# SDRAM.net
KiCad netlist of a schematic drawn in Altium Designer
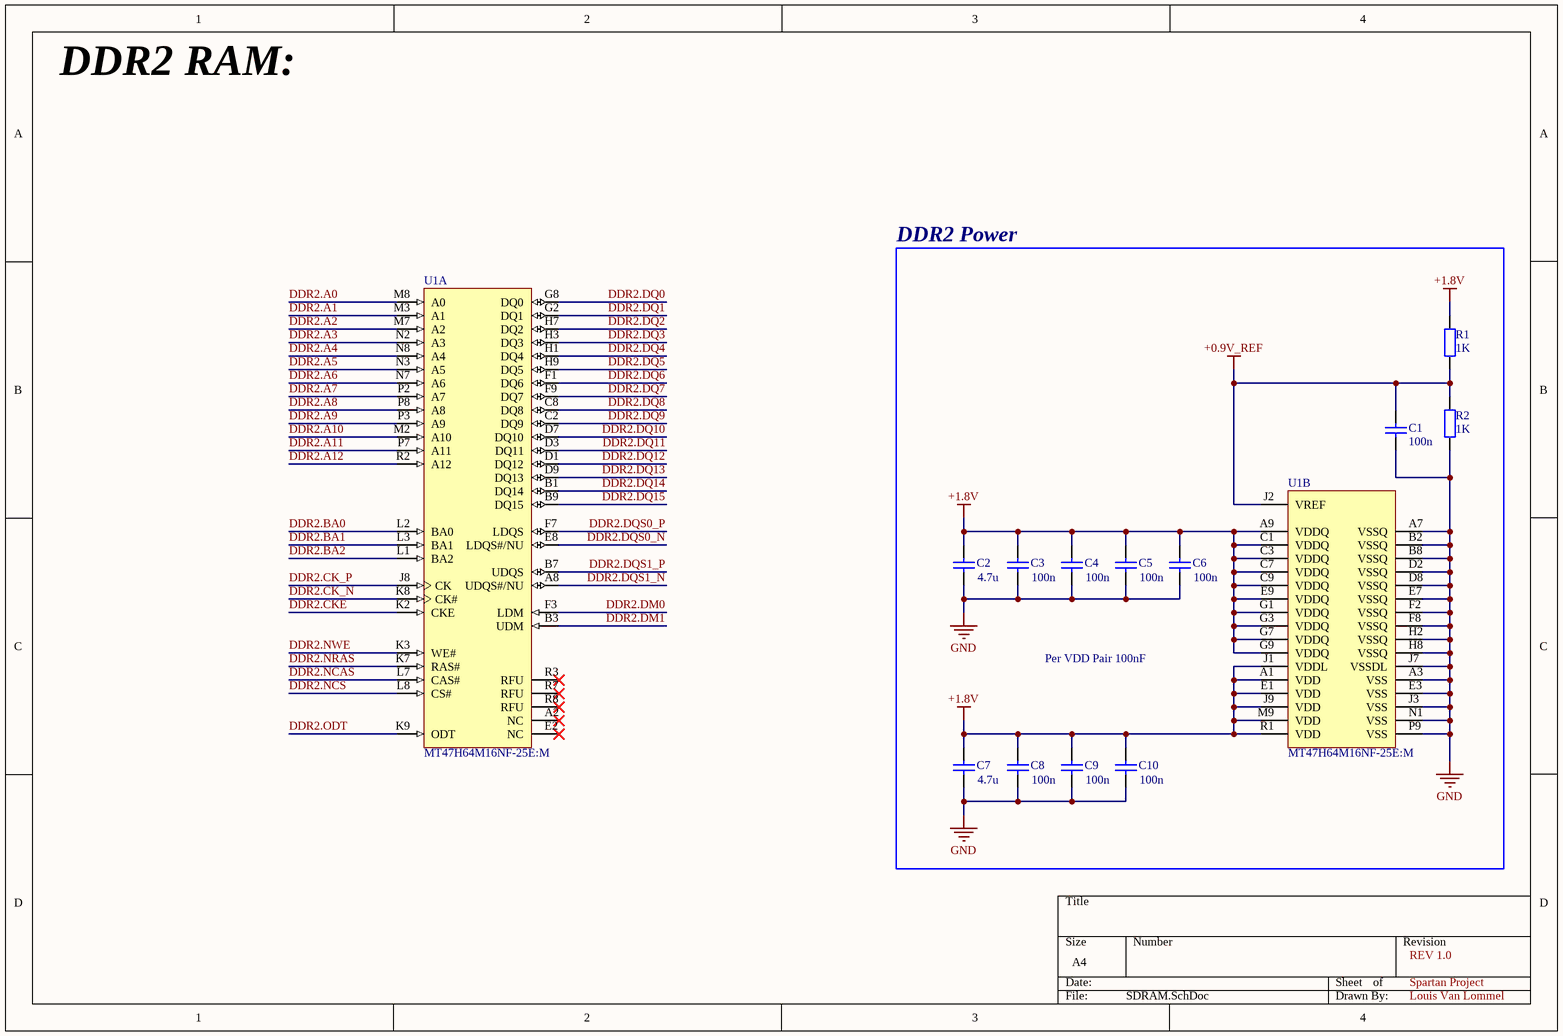
[diagram p0: SDRAM.SchDoc]

(export (version "E")
  (design (tool "Eeschema 10.0.6"))
  (components
    (comp (ref "C1")
      (value "100n")
      (footprint "CAP_0603")
      (description "Capacitor")
      (fields (field (name "PUBLISHER") "Altium Limited"))
      (libsource (lib "Miscellaneous Devices") (part "Cap"))
    )
    (comp (ref "C2")
      (value "4.7u")
      (description "Capacitor")
      (fields (field (name "PUBLISHER") "Altium Limited"))
      (libsource (lib "Miscellaneous Devices") (part "Cap"))
    )
    (comp (ref "C3")
      (value "100n")
      (footprint "CAP_0603")
      (description "Capacitor")
      (fields (field (name "PUBLISHER") "Altium Limited"))
      (libsource (lib "Miscellaneous Devices") (part "Cap"))
    )
    (comp (ref "C4")
      (value "100n")
      (footprint "CAP_0603")
      (description "Capacitor")
      (fields (field (name "PUBLISHER") "Altium Limited"))
      (libsource (lib "Miscellaneous Devices") (part "Cap"))
    )
    (comp (ref "C5")
      (value "100n")
      (footprint "CAP_0603")
      (description "Capacitor")
      (fields (field (name "PUBLISHER") "Altium Limited"))
      (libsource (lib "Miscellaneous Devices") (part "Cap"))
    )
    (comp (ref "C6")
      (value "100n")
      (footprint "CAP_0603")
      (description "Capacitor")
      (fields (field (name "PUBLISHER") "Altium Limited"))
      (libsource (lib "Miscellaneous Devices") (part "Cap"))
    )
    (comp (ref "C7")
      (value "4.7u")
      (description "Capacitor")
      (fields (field (name "PUBLISHER") "Altium Limited"))
      (libsource (lib "Miscellaneous Devices") (part "Cap"))
    )
    (comp (ref "C8")
      (value "100n")
      (footprint "CAP_0603")
      (description "Capacitor")
      (fields (field (name "PUBLISHER") "Altium Limited"))
      (libsource (lib "Miscellaneous Devices") (part "Cap"))
    )
    (comp (ref "C9")
      (value "100n")
      (footprint "CAP_0603")
      (description "Capacitor")
      (fields (field (name "PUBLISHER") "Altium Limited"))
      (libsource (lib "Miscellaneous Devices") (part "Cap"))
    )
    (comp (ref "C10")
      (value "100n")
      (footprint "CAP_0603")
      (description "Capacitor")
      (fields (field (name "PUBLISHER") "Altium Limited"))
      (libsource (lib "Miscellaneous Devices") (part "Cap"))
    )
    (comp (ref "R1")
      (value "1K")
      (footprint "RES_0603")
      (description "Resistor")
      (fields (field (name "PUBLISHER") "Altium Limited"))
      (libsource (lib "") (part "Res2_1"))
    )
    (comp (ref "R2")
      (value "1K")
      (footprint "RES_0603")
      (description "Resistor")
      (fields (field (name "PUBLISHER") "Altium Limited"))
      (libsource (lib "Miscellaneous Devices") (part "Res2"))
    )
    (comp (ref "U1")
      (value "MT47H64M16NF-25E:M")
      (footprint "MICT-NF-84")
      (description "1 Gb DDR2-800 SDRAM, 64 Mb x 16, 2.5 ns, 1.8 V, 0 to 85 degC, 84-Ball FBGA, Pb-Free")
      (fields (field (name "MANUFACTURER") "Micron"))
      (libsource (lib "Altium Content Vault") (part "MICT-MT47HXXMXXNF-84"))
    )
  )
  (nets
    (net (code "1") (name "+0.9V_REF") (class "Default")
      (node (ref "C1") (pin "2") (pinfunction "2_2") (pintype "passive"))
      (node (ref "R1") (pin "2") (pinfunction "2_2") (pintype "passive"))
      (node (ref "R2") (pin "2") (pinfunction "2_2") (pintype "passive"))
      (node (ref "U1") (pin "J2") (pinfunction "VREF_J2") (pintype "power_in"))
    )
    (net (code "2") (name "+1.8V") (class "Default")
      (node (ref "C10") (pin "2") (pinfunction "2_2") (pintype "passive"))
      (node (ref "C2") (pin "2") (pinfunction "2_2") (pintype "passive"))
      (node (ref "C3") (pin "2") (pinfunction "2_2") (pintype "passive"))
      (node (ref "C4") (pin "2") (pinfunction "2_2") (pintype "passive"))
      (node (ref "C5") (pin "2") (pinfunction "2_2") (pintype "passive"))
      (node (ref "C6") (pin "2") (pinfunction "2_2") (pintype "passive"))
      (node (ref "C7") (pin "2") (pinfunction "2_2") (pintype "passive"))
      (node (ref "C8") (pin "2") (pinfunction "2_2") (pintype "passive"))
      (node (ref "C9") (pin "2") (pinfunction "2_2") (pintype "passive"))
      (node (ref "R1") (pin "1") (pinfunction "1_1") (pintype "passive"))
      (node (ref "U1") (pin "A1") (pinfunction "VDD_A1") (pintype "power_in"))
      (node (ref "U1") (pin "A9") (pinfunction "VDDQ_A9") (pintype "power_in"))
      (node (ref "U1") (pin "C1") (pinfunction "VDDQ_C1") (pintype "power_in"))
      (node (ref "U1") (pin "C3") (pinfunction "VDDQ_C3") (pintype "power_in"))
      (node (ref "U1") (pin "C7") (pinfunction "VDDQ_C7") (pintype "power_in"))
      (node (ref "U1") (pin "C9") (pinfunction "VDDQ_C9") (pintype "power_in"))
      (node (ref "U1") (pin "E1") (pinfunction "VDD_E1") (pintype "power_in"))
      (node (ref "U1") (pin "E9") (pinfunction "VDDQ_E9") (pintype "power_in"))
      (node (ref "U1") (pin "G1") (pinfunction "VDDQ_G1") (pintype "power_in"))
      (node (ref "U1") (pin "G3") (pinfunction "VDDQ_G3") (pintype "power_in"))
      (node (ref "U1") (pin "G7") (pinfunction "VDDQ_G7") (pintype "power_in"))
      (node (ref "U1") (pin "G9") (pinfunction "VDDQ_G9") (pintype "power_in"))
      (node (ref "U1") (pin "J1") (pinfunction "VDDL_J1") (pintype "power_in"))
      (node (ref "U1") (pin "J9") (pinfunction "VDD_J9") (pintype "power_in"))
      (node (ref "U1") (pin "M9") (pinfunction "VDD_M9") (pintype "power_in"))
      (node (ref "U1") (pin "R1") (pinfunction "VDD_R1") (pintype "power_in"))
    )
    (net (code "3") (name "/DDR2.A0") (class "Default")
      (node (ref "U1") (pin "M8") (pinfunction "A0_M8") (pintype "input"))
    )
    (net (code "4") (name "/DDR2.A1") (class "Default")
      (node (ref "U1") (pin "M3") (pinfunction "A1_M3") (pintype "input"))
    )
    (net (code "5") (name "/DDR2.A2") (class "Default")
      (node (ref "U1") (pin "M7") (pinfunction "A2_M7") (pintype "input"))
    )
    (net (code "6") (name "/DDR2.A3") (class "Default")
      (node (ref "U1") (pin "N2") (pinfunction "A3_N2") (pintype "input"))
    )
    (net (code "7") (name "/DDR2.A4") (class "Default")
      (node (ref "U1") (pin "N8") (pinfunction "A4_N8") (pintype "input"))
    )
    (net (code "8") (name "/DDR2.A5") (class "Default")
      (node (ref "U1") (pin "N3") (pinfunction "A5_N3") (pintype "input"))
    )
    (net (code "9") (name "/DDR2.A6") (class "Default")
      (node (ref "U1") (pin "N7") (pinfunction "A6_N7") (pintype "input"))
    )
    (net (code "10") (name "/DDR2.A7") (class "Default")
      (node (ref "U1") (pin "P2") (pinfunction "A7_P2") (pintype "input"))
    )
    (net (code "11") (name "/DDR2.A8") (class "Default")
      (node (ref "U1") (pin "P8") (pinfunction "A8_P8") (pintype "input"))
    )
    (net (code "12") (name "/DDR2.A9") (class "Default")
      (node (ref "U1") (pin "P3") (pinfunction "A9_P3") (pintype "input"))
    )
    (net (code "13") (name "/DDR2.A10") (class "Default")
      (node (ref "U1") (pin "M2") (pinfunction "A10_M2") (pintype "input"))
    )
    (net (code "14") (name "/DDR2.A11") (class "Default")
      (node (ref "U1") (pin "P7") (pinfunction "A11_P7") (pintype "input"))
    )
    (net (code "15") (name "/DDR2.A12") (class "Default")
      (node (ref "U1") (pin "R2") (pinfunction "A12_R2") (pintype "input"))
    )
    (net (code "16") (name "/DDR2.BA0") (class "Default")
      (node (ref "U1") (pin "L2") (pinfunction "BA0_L2") (pintype "input"))
    )
    (net (code "17") (name "/DDR2.BA1") (class "Default")
      (node (ref "U1") (pin "L3") (pinfunction "BA1_L3") (pintype "input"))
    )
    (net (code "18") (name "/DDR2.BA2") (class "Default")
      (node (ref "U1") (pin "L1") (pinfunction "BA2_L1") (pintype "input"))
    )
    (net (code "19") (name "/DDR2.CKE") (class "Default")
      (node (ref "U1") (pin "K2") (pinfunction "CKE_K2") (pintype "input"))
    )
    (net (code "20") (name "/DDR2.CK_N") (class "Default")
      (node (ref "U1") (pin "K8") (pinfunction "CK#_K8") (pintype "input"))
    )
    (net (code "21") (name "/DDR2.CK_P") (class "Default")
      (node (ref "U1") (pin "J8") (pinfunction "CK_J8") (pintype "input"))
    )
    (net (code "22") (name "/DDR2.DM0") (class "Default")
      (node (ref "U1") (pin "F3") (pinfunction "LDM_F3") (pintype "input"))
    )
    (net (code "23") (name "/DDR2.DM1") (class "Default")
      (node (ref "U1") (pin "B3") (pinfunction "UDM_B3") (pintype "input"))
    )
    (net (code "24") (name "/DDR2.DQ0") (class "Default")
      (node (ref "U1") (pin "G8") (pinfunction "DQ0_G8") (pintype "bidirectional"))
    )
    (net (code "25") (name "/DDR2.DQ1") (class "Default")
      (node (ref "U1") (pin "G2") (pinfunction "DQ1_G2") (pintype "bidirectional"))
    )
    (net (code "26") (name "/DDR2.DQ2") (class "Default")
      (node (ref "U1") (pin "H7") (pinfunction "DQ2_H7") (pintype "bidirectional"))
    )
    (net (code "27") (name "/DDR2.DQ3") (class "Default")
      (node (ref "U1") (pin "H3") (pinfunction "DQ3_H3") (pintype "bidirectional"))
    )
    (net (code "28") (name "/DDR2.DQ4") (class "Default")
      (node (ref "U1") (pin "H1") (pinfunction "DQ4_H1") (pintype "bidirectional"))
    )
    (net (code "29") (name "/DDR2.DQ5") (class "Default")
      (node (ref "U1") (pin "H9") (pinfunction "DQ5_H9") (pintype "bidirectional"))
    )
    (net (code "30") (name "/DDR2.DQ6") (class "Default")
      (node (ref "U1") (pin "F1") (pinfunction "DQ6_F1") (pintype "bidirectional"))
    )
    (net (code "31") (name "/DDR2.DQ7") (class "Default")
      (node (ref "U1") (pin "F9") (pinfunction "DQ7_F9") (pintype "bidirectional"))
    )
    (net (code "32") (name "/DDR2.DQ8") (class "Default")
      (node (ref "U1") (pin "C8") (pinfunction "DQ8_C8") (pintype "bidirectional"))
    )
    (net (code "33") (name "/DDR2.DQ9") (class "Default")
      (node (ref "U1") (pin "C2") (pinfunction "DQ9_C2") (pintype "bidirectional"))
    )
    (net (code "34") (name "/DDR2.DQ10") (class "Default")
      (node (ref "U1") (pin "D7") (pinfunction "DQ10_D7") (pintype "bidirectional"))
    )
    (net (code "35") (name "/DDR2.DQ11") (class "Default")
      (node (ref "U1") (pin "D3") (pinfunction "DQ11_D3") (pintype "bidirectional"))
    )
    (net (code "36") (name "/DDR2.DQ12") (class "Default")
      (node (ref "U1") (pin "D1") (pinfunction "DQ12_D1") (pintype "bidirectional"))
    )
    (net (code "37") (name "/DDR2.DQ13") (class "Default")
      (node (ref "U1") (pin "D9") (pinfunction "DQ13_D9") (pintype "bidirectional"))
    )
    (net (code "38") (name "/DDR2.DQ14") (class "Default")
      (node (ref "U1") (pin "B1") (pinfunction "DQ14_B1") (pintype "bidirectional"))
    )
    (net (code "39") (name "/DDR2.DQ15") (class "Default")
      (node (ref "U1") (pin "B9") (pinfunction "DQ15_B9") (pintype "bidirectional"))
    )
    (net (code "40") (name "/DDR2.DQS0_N") (class "Default")
      (node (ref "U1") (pin "E8") (pinfunction "LDQS#/NU_E8") (pintype "bidirectional"))
    )
    (net (code "41") (name "/DDR2.DQS0_P") (class "Default")
      (node (ref "U1") (pin "F7") (pinfunction "LDQS_F7") (pintype "bidirectional"))
    )
    (net (code "42") (name "/DDR2.DQS1_N") (class "Default")
      (node (ref "U1") (pin "A8") (pinfunction "UDQS#/NU_A8") (pintype "bidirectional"))
    )
    (net (code "43") (name "/DDR2.DQS1_P") (class "Default")
      (node (ref "U1") (pin "B7") (pinfunction "UDQS_B7") (pintype "bidirectional"))
    )
    (net (code "44") (name "/DDR2.NCAS") (class "Default")
      (node (ref "U1") (pin "L7") (pinfunction "CAS#_L7") (pintype "input"))
    )
    (net (code "45") (name "/DDR2.NCS") (class "Default")
      (node (ref "U1") (pin "L8") (pinfunction "CS#_L8") (pintype "input"))
    )
    (net (code "46") (name "/DDR2.NRAS") (class "Default")
      (node (ref "U1") (pin "K7") (pinfunction "RAS#_K7") (pintype "input"))
    )
    (net (code "47") (name "/DDR2.NWE") (class "Default")
      (node (ref "U1") (pin "K3") (pinfunction "WE#_K3") (pintype "input"))
    )
    (net (code "48") (name "/DDR2.ODT") (class "Default")
      (node (ref "U1") (pin "K9") (pinfunction "ODT_K9") (pintype "input"))
    )
    (net (code "49") (name "GND") (class "Default")
      (node (ref "C1") (pin "1") (pinfunction "1_1") (pintype "passive"))
      (node (ref "C10") (pin "1") (pinfunction "1_1") (pintype "passive"))
      (node (ref "C2") (pin "1") (pinfunction "1_1") (pintype "passive"))
      (node (ref "C3") (pin "1") (pinfunction "1_1") (pintype "passive"))
      (node (ref "C4") (pin "1") (pinfunction "1_1") (pintype "passive"))
      (node (ref "C5") (pin "1") (pinfunction "1_1") (pintype "passive"))
      (node (ref "C6") (pin "1") (pinfunction "1_1") (pintype "passive"))
      (node (ref "C7") (pin "1") (pinfunction "1_1") (pintype "passive"))
      (node (ref "C8") (pin "1") (pinfunction "1_1") (pintype "passive"))
      (node (ref "C9") (pin "1") (pinfunction "1_1") (pintype "passive"))
      (node (ref "R2") (pin "1") (pinfunction "1_1") (pintype "passive"))
      (node (ref "U1") (pin "A3") (pinfunction "VSS_A3") (pintype "power_in"))
      (node (ref "U1") (pin "A7") (pinfunction "VSSQ_A7") (pintype "power_in"))
      (node (ref "U1") (pin "B2") (pinfunction "VSSQ_B2") (pintype "power_in"))
      (node (ref "U1") (pin "B8") (pinfunction "VSSQ_B8") (pintype "power_in"))
      (node (ref "U1") (pin "D2") (pinfunction "VSSQ_D2") (pintype "power_in"))
      (node (ref "U1") (pin "D8") (pinfunction "VSSQ_D8") (pintype "power_in"))
      (node (ref "U1") (pin "E3") (pinfunction "VSS_E3") (pintype "power_in"))
      (node (ref "U1") (pin "E7") (pinfunction "VSSQ_E7") (pintype "power_in"))
      (node (ref "U1") (pin "F2") (pinfunction "VSSQ_F2") (pintype "power_in"))
      (node (ref "U1") (pin "F8") (pinfunction "VSSQ_F8") (pintype "power_in"))
      (node (ref "U1") (pin "H2") (pinfunction "VSSQ_H2") (pintype "power_in"))
      (node (ref "U1") (pin "H8") (pinfunction "VSSQ_H8") (pintype "power_in"))
      (node (ref "U1") (pin "J3") (pinfunction "VSS_J3") (pintype "power_in"))
      (node (ref "U1") (pin "J7") (pinfunction "VSSDL_J7") (pintype "power_in"))
      (node (ref "U1") (pin "N1") (pinfunction "VSS_N1") (pintype "power_in"))
      (node (ref "U1") (pin "P9") (pinfunction "VSS_P9") (pintype "power_in"))
    )
    (net (code "50") (name "unconnected-(U1A-NC-PadA2)") (class "Default")
      (node (ref "U1") (pin "A2") (pinfunction "NC_A2") (pintype "passive+no_connect"))
    )
    (net (code "51") (name "unconnected-(U1A-NC-PadE2)") (class "Default")
      (node (ref "U1") (pin "E2") (pinfunction "NC_E2") (pintype "passive+no_connect"))
    )
    (net (code "52") (name "unconnected-(U1A-RFU-PadR3)") (class "Default")
      (node (ref "U1") (pin "R3") (pinfunction "RFU_R3") (pintype "passive+no_connect"))
    )
    (net (code "53") (name "unconnected-(U1A-RFU-PadR7)") (class "Default")
      (node (ref "U1") (pin "R7") (pinfunction "RFU_R7") (pintype "passive+no_connect"))
    )
    (net (code "54") (name "unconnected-(U1A-RFU-PadR8)") (class "Default")
      (node (ref "U1") (pin "R8") (pinfunction "RFU_R8") (pintype "passive+no_connect"))
    )
  )
)
